# Sheet_1_2025-08-10.net
KiCad netlist of a schematic drawn in Altium Designer
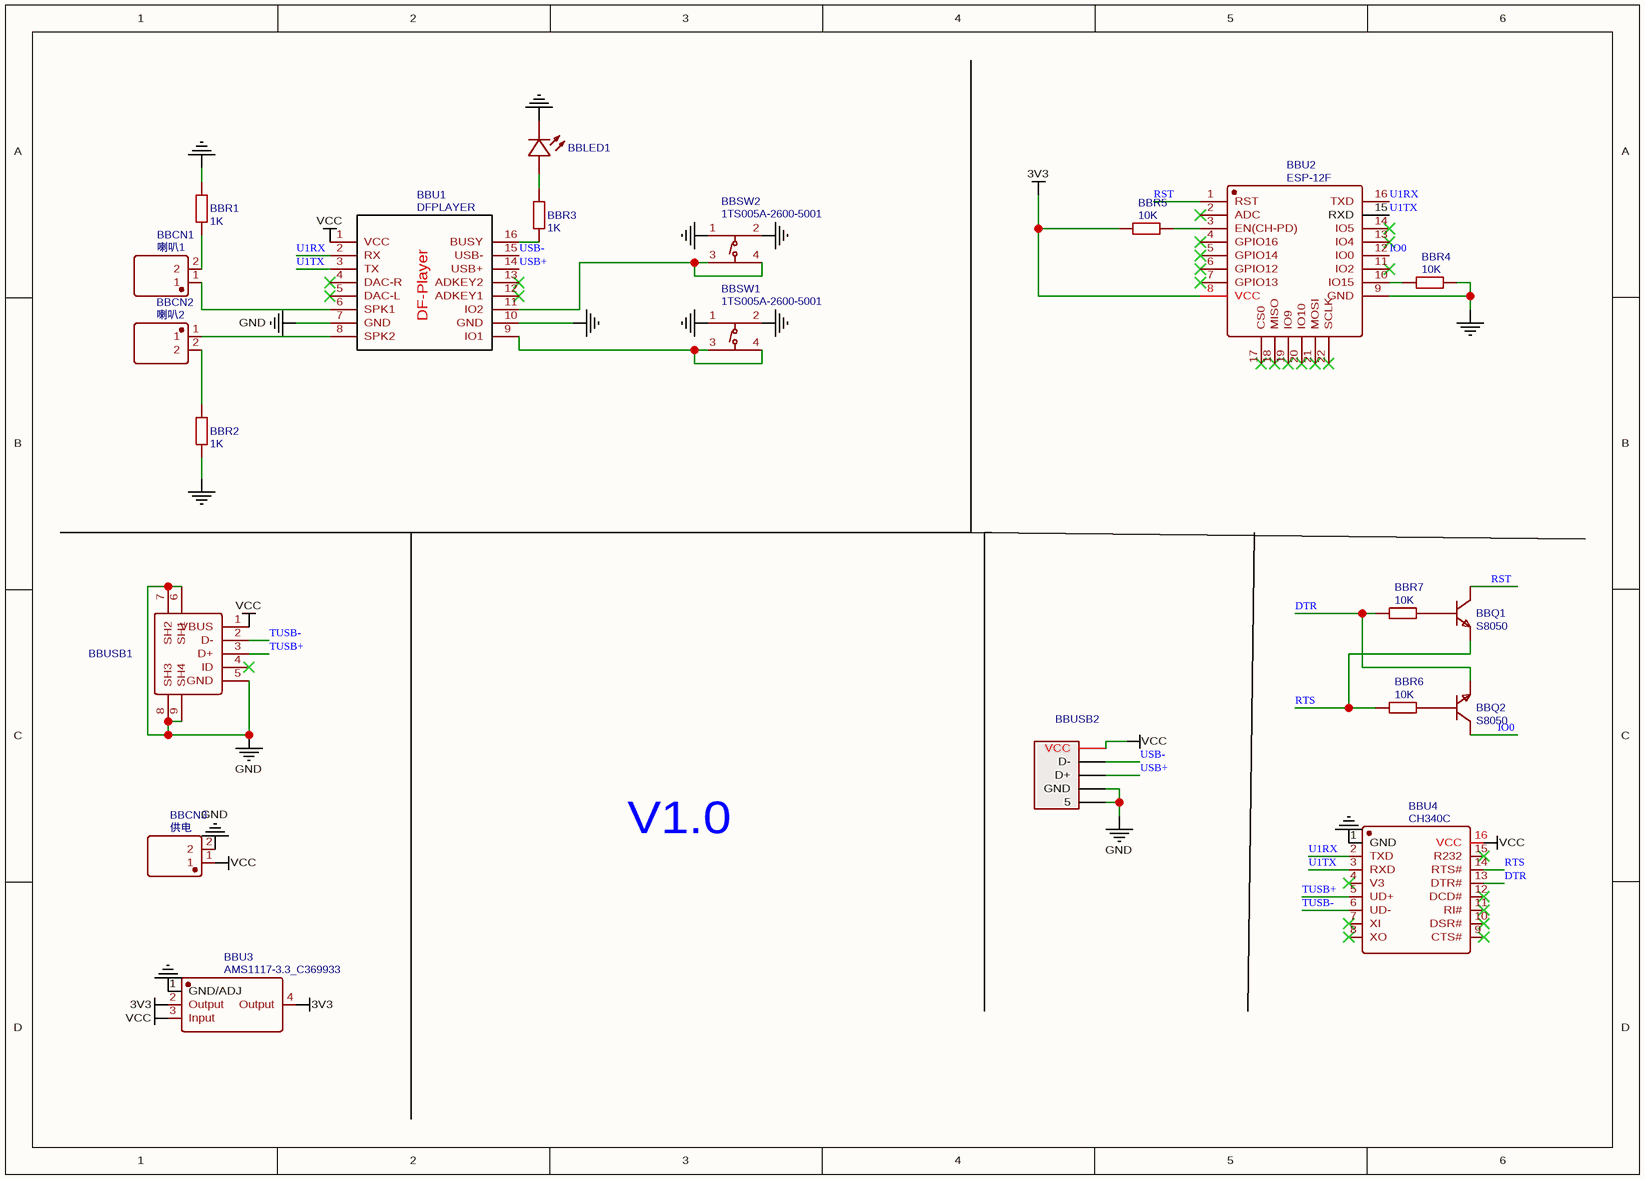
[diagram p0: Sheet_1_2025-08-10.schdoc]

(export (version "E")
  (design (tool "Eeschema 10.0.6"))
  (components
    (comp (ref "BBCN1")
      (value "喇叭1")
      (fields (field (name "MANUFACTURER") "Boom Precision Elec") (field (name "CONTRIBUTOR") "LCSC"))
      (libsource (lib "altium-import") (part "root_2_喇叭1_"))
    )
    (comp (ref "BBCN2")
      (value "喇叭2")
      (fields (field (name "MANUFACTURER") "Boom Precision Elec") (field (name "CONTRIBUTOR") "LCSC"))
      (libsource (lib "altium-import") (part "root_2_喇叭2_"))
    )
    (comp (ref "BBCN3")
      (value "供电")
      (fields (field (name "MANUFACTURER") "Boom Precision Elec") (field (name "CONTRIBUTOR") "LCSC"))
      (libsource (lib "altium-import") (part "root_2_供电_"))
    )
    (comp (ref "BBLED1")
      (value "FC-2012WBY-460G")
      (fields (field (name "MANUFACTURER") "NATIONSTAR"))
      (libsource (lib "altium-import") (part "root_3_FC-2012WBY-460G_"))
    )
    (comp (ref "BBQ1")
      (value "S8050")
      (fields (field (name "MANUFACTURER") "Yenji") (field (name "CONTRIBUTOR") "立创EDA官方封装库"))
      (libsource (lib "") (part "root_0_S8050__1"))
    )
    (comp (ref "BBQ2")
      (value "S8050")
      (fields (field (name "MANUFACTURER") "Yenji") (field (name "CONTRIBUTOR") "立创EDA官方封装库"))
      (libsource (lib "altium-import") (part "root_0_S8050_"))
    )
    (comp (ref "BBR1")
      (value "1K")
      (fields
        (field (name "MANUFACTURER") "LIZ Elec")
        (field (name "MANUFACTURER PART") "CR0805J80102G")
        (field (name "CONTRIBUTOR") "LCSC")
      )
      (libsource (lib "altium-import") (part "root_1_1K_"))
    )
    (comp (ref "BBR2")
      (value "1K")
      (fields
        (field (name "MANUFACTURER") "LIZ Elec")
        (field (name "MANUFACTURER PART") "CR0805J80102G")
        (field (name "CONTRIBUTOR") "LCSC")
      )
      (libsource (lib "altium-import") (part "root_3_1K_"))
    )
    (comp (ref "BBR3")
      (value "1K")
      (fields
        (field (name "MANUFACTURER") "LIZ Elec")
        (field (name "MANUFACTURER PART") "CR0805J80102G")
        (field (name "CONTRIBUTOR") "LCSC")
      )
      (libsource (lib "altium-import") (part "root_1_1K_"))
    )
    (comp (ref "BBR4")
      (value "10K")
      (fields
        (field (name "MANUFACTURER") "Stackpole Elec")
        (field (name "MANUFACTURER PART") "RMCF0603JT10K0")
        (field (name "CONTRIBUTOR") "LCSC")
      )
      (libsource (lib "altium-import") (part "root_0_10K_"))
    )
    (comp (ref "BBR5")
      (value "10K")
      (fields
        (field (name "MANUFACTURER") "Stackpole Elec")
        (field (name "MANUFACTURER PART") "RMCF0603JT10K0")
        (field (name "CONTRIBUTOR") "LCSC")
      )
      (libsource (lib "altium-import") (part "root_0_10K_"))
    )
    (comp (ref "BBR6")
      (value "10K")
      (fields
        (field (name "MANUFACTURER") "Stackpole Elec")
        (field (name "MANUFACTURER PART") "RMCF0603JT10K0")
        (field (name "CONTRIBUTOR") "LCSC")
      )
      (libsource (lib "altium-import") (part "root_0_10K_"))
    )
    (comp (ref "BBR7")
      (value "10K")
      (fields
        (field (name "MANUFACTURER") "Stackpole Elec")
        (field (name "MANUFACTURER PART") "RMCF0603JT10K0")
        (field (name "CONTRIBUTOR") "LCSC")
      )
      (libsource (lib "altium-import") (part "root_0_10K_"))
    )
    (comp (ref "BBSW1")
      (value "1TS005A-2600-5001")
      (fields (field (name "MANUFACTURER") "HYP") (field (name "CONTRIBUTOR") "LCSC"))
      (libsource (lib "altium-import") (part "root_0_1TS005A-2600-5001_"))
    )
    (comp (ref "BBSW2")
      (value "1TS005A-2600-5001")
      (fields (field (name "MANUFACTURER") "HYP") (field (name "CONTRIBUTOR") "LCSC"))
      (libsource (lib "altium-import") (part "root_0_1TS005A-2600-5001_"))
    )
    (comp (ref "BBU1")
      (value "DFPLAYER")
      (fields (field (name "CONTRIBUTOR") "walter471114"))
      (libsource (lib "altium-import") (part "root_0_DFPLAYER_"))
    )
    (comp (ref "BBU2")
      (value "ESP-12F")
      (fields
        (field (name "MANUFACTURER") "Ai-Thinker")
        (field (name "MANUFACTURER PART") "ESP-12F(ESP8266MOD)")
      )
      (libsource (lib "altium-import") (part "root_0_ESP-12F_"))
    )
    (comp (ref "BBU3")
      (value "AMS1117-3.3_C369933")
      (fields
        (field (name "MANUFACTURER") "KEXIN")
        (field (name "MANUFACTURER PART") "AMS1117-3.3")
        (field (name "CONTRIBUTOR") "LCSC")
      )
      (libsource (lib "altium-import") (part "root_0_AMS1117-3.3_C369933_"))
    )
    (comp (ref "BBU4")
      (value "CH340C")
      (fields (field (name "MANUFACTURER") "WCH"))
      (libsource (lib "altium-import") (part "root_0_CH340C_"))
    )
    (comp (ref "BBUSB1")
      (value "MICROQTJ")
      (fields
        (field (name "MANUFACTURER") "SHOU HAN")
        (field (name "MANUFACTURER PART") "MicroQTJ")
        (field (name "CONTRIBUTOR") "LCSC")
      )
      (libsource (lib "altium-import") (part "root_0_MICROQTJ_"))
    )
    (comp (ref "BBUSB2")
      (value "YJ-USB-AF-SMT-01")
      (fields (field (name "MANUFACTURER") "ValuePro"))
      (libsource (lib "altium-import") (part "root_0_YJ-USB-AF-SMT-01_"))
    )
  )
  (nets
    (net (code "1") (name "/DTR") (class "Default")
      (node (ref "BBQ2") (pin "2") (pinfunction "E_2") (pintype "passive"))
      (node (ref "BBR7") (pin "1") (pinfunction "1_1") (pintype "passive"))
      (node (ref "BBU4") (pin "13") (pinfunction "DTR#_13") (pintype "passive"))
    )
    (net (code "2") (name "/IO0") (class "Default")
      (node (ref "BBQ2") (pin "3") (pinfunction "C_3") (pintype "passive"))
      (node (ref "BBU2") (pin "12") (pinfunction "IO0_12") (pintype "passive"))
    )
    (net (code "3") (name "/RST") (class "Default")
      (node (ref "BBQ1") (pin "3") (pinfunction "C_3") (pintype "passive"))
      (node (ref "BBU2") (pin "1") (pinfunction "RST_1") (pintype "passive"))
    )
    (net (code "4") (name "/RTS") (class "Default")
      (node (ref "BBQ1") (pin "2") (pinfunction "E_2") (pintype "passive"))
      (node (ref "BBR6") (pin "1") (pinfunction "1_1") (pintype "passive"))
      (node (ref "BBU4") (pin "14") (pinfunction "RTS#_14") (pintype "passive"))
    )
    (net (code "5") (name "/TUSB+") (class "Default")
      (node (ref "BBU4") (pin "5") (pinfunction "UD+_5") (pintype "passive"))
      (node (ref "BBUSB1") (pin "3") (pinfunction "D+_3") (pintype "passive"))
    )
    (net (code "6") (name "/TUSB-") (class "Default")
      (node (ref "BBU4") (pin "6") (pinfunction "UD-_6") (pintype "passive"))
      (node (ref "BBUSB1") (pin "2") (pinfunction "D-_2") (pintype "passive"))
    )
    (net (code "7") (name "/U1RX") (class "Default")
      (node (ref "BBU1") (pin "2") (pinfunction "RX_2") (pintype "passive"))
      (node (ref "BBU2") (pin "16") (pinfunction "TXD_16") (pintype "passive"))
      (node (ref "BBU4") (pin "2") (pinfunction "TXD_2") (pintype "passive"))
    )
    (net (code "8") (name "/U1TX") (class "Default")
      (node (ref "BBU1") (pin "3") (pinfunction "TX_3") (pintype "passive"))
      (node (ref "BBU2") (pin "15") (pinfunction "RXD_15") (pintype "passive"))
      (node (ref "BBU4") (pin "3") (pinfunction "RXD_3") (pintype "passive"))
    )
    (net (code "9") (name "/USB+") (class "Default")
      (node (ref "BBU1") (pin "14") (pinfunction "USB+_14") (pintype "passive"))
      (node (ref "BBUSB2") (pin "3") (pinfunction "D+_3") (pintype "passive"))
    )
    (net (code "10") (name "/USB-") (class "Default")
      (node (ref "BBU1") (pin "15") (pinfunction "USB-_15") (pintype "passive"))
      (node (ref "BBUSB2") (pin "2") (pinfunction "D-_2") (pintype "passive"))
    )
    (net (code "11") (name "3V3") (class "Default")
      (node (ref "BBR5") (pin "1") (pinfunction "1_1") (pintype "passive"))
      (node (ref "BBU2") (pin "8") (pinfunction "VCC_8") (pintype "passive"))
      (node (ref "BBU3") (pin "2") (pinfunction "Output_2") (pintype "passive"))
      (node (ref "BBU3") (pin "4") (pinfunction "Output_4") (pintype "passive"))
    )
    (net (code "12") (name "GND") (class "Default")
      (node (ref "BBCN3") (pin "2") (pinfunction "2_2") (pintype "passive"))
      (node (ref "BBLED1") (pin "1") (pinfunction "-_1") (pintype "passive"))
      (node (ref "BBR1") (pin "2") (pinfunction "2_2") (pintype "passive"))
      (node (ref "BBR2") (pin "2") (pinfunction "2_2") (pintype "passive"))
      (node (ref "BBR4") (pin "2") (pinfunction "2_2") (pintype "passive"))
      (node (ref "BBSW1") (pin "1") (pinfunction "1_1") (pintype "passive"))
      (node (ref "BBSW1") (pin "2") (pinfunction "2_2") (pintype "passive"))
      (node (ref "BBSW2") (pin "1") (pinfunction "1_1") (pintype "passive"))
      (node (ref "BBSW2") (pin "2") (pinfunction "2_2") (pintype "passive"))
      (node (ref "BBU1") (pin "10") (pinfunction "GND_10") (pintype "passive"))
      (node (ref "BBU1") (pin "7") (pinfunction "GND_7") (pintype "passive"))
      (node (ref "BBU2") (pin "9") (pinfunction "GND_9") (pintype "passive"))
      (node (ref "BBU3") (pin "1") (pinfunction "GND/ADJ_1") (pintype "passive"))
      (node (ref "BBU4") (pin "1") (pinfunction "GND_1") (pintype "passive"))
      (node (ref "BBUSB1") (pin "5") (pinfunction "GND_5") (pintype "passive"))
      (node (ref "BBUSB1") (pin "6") (pinfunction "SH1_6") (pintype "passive"))
      (node (ref "BBUSB1") (pin "7") (pinfunction "SH2_7") (pintype "passive"))
      (node (ref "BBUSB1") (pin "8") (pinfunction "SH3_8") (pintype "passive"))
      (node (ref "BBUSB1") (pin "9") (pinfunction "SH4_9") (pintype "passive"))
      (node (ref "BBUSB2") (pin "4") (pinfunction "GND_4") (pintype "passive"))
      (node (ref "BBUSB2") (pin "5") (pinfunction "5_5") (pintype "passive"))
    )
    (net (code "13") (name "Net-(BBCN1-Pad2)") (class "Default")
      (node (ref "BBCN1") (pin "2") (pinfunction "2_2") (pintype "passive"))
      (node (ref "BBR1") (pin "1") (pinfunction "1_1") (pintype "passive"))
    )
    (net (code "14") (name "Net-(BBCN2-Pad2)") (class "Default")
      (node (ref "BBCN2") (pin "2") (pinfunction "2_2") (pintype "passive"))
      (node (ref "BBR2") (pin "1") (pinfunction "1_1") (pintype "passive"))
    )
    (net (code "15") (name "Net-(BBLED1-+)") (class "Default")
      (node (ref "BBLED1") (pin "2") (pinfunction "+_2") (pintype "passive"))
      (node (ref "BBR3") (pin "2") (pinfunction "2_2") (pintype "passive"))
    )
    (net (code "16") (name "Net-(BBQ1-B)") (class "Default")
      (node (ref "BBQ1") (pin "1") (pinfunction "B_1") (pintype "passive"))
      (node (ref "BBR7") (pin "2") (pinfunction "2_2") (pintype "passive"))
    )
    (net (code "17") (name "Net-(BBQ2-B)") (class "Default")
      (node (ref "BBQ2") (pin "1") (pinfunction "B_1") (pintype "passive"))
      (node (ref "BBR6") (pin "2") (pinfunction "2_2") (pintype "passive"))
    )
    (net (code "18") (name "Net-(BBU1-BUSY)") (class "Default")
      (node (ref "BBR3") (pin "1") (pinfunction "1_1") (pintype "passive"))
      (node (ref "BBU1") (pin "16") (pinfunction "BUSY_16") (pintype "passive"))
    )
    (net (code "19") (name "Net-(BBU1-IO1)") (class "Default")
      (node (ref "BBSW1") (pin "3") (pinfunction "3_3") (pintype "passive"))
      (node (ref "BBSW1") (pin "4") (pinfunction "4_4") (pintype "passive"))
      (node (ref "BBU1") (pin "9") (pinfunction "IO1_9") (pintype "passive"))
    )
    (net (code "20") (name "Net-(BBU1-IO2)") (class "Default")
      (node (ref "BBSW2") (pin "3") (pinfunction "3_3") (pintype "passive"))
      (node (ref "BBSW2") (pin "4") (pinfunction "4_4") (pintype "passive"))
      (node (ref "BBU1") (pin "11") (pinfunction "IO2_11") (pintype "passive"))
    )
    (net (code "21") (name "Net-(BBU1-SPK1)") (class "Default")
      (node (ref "BBCN1") (pin "1") (pinfunction "1_1") (pintype "passive"))
      (node (ref "BBU1") (pin "6") (pinfunction "SPK1_6") (pintype "passive"))
    )
    (net (code "22") (name "Net-(BBU1-SPK2)") (class "Default")
      (node (ref "BBCN2") (pin "1") (pinfunction "1_1") (pintype "passive"))
      (node (ref "BBU1") (pin "8") (pinfunction "SPK2_8") (pintype "passive"))
    )
    (net (code "23") (name "Net-(BBU2-EN(CH-PD))") (class "Default")
      (node (ref "BBR5") (pin "2") (pinfunction "2_2") (pintype "passive"))
      (node (ref "BBU2") (pin "3") (pinfunction "EN(CH-PD)_3") (pintype "passive"))
    )
    (net (code "24") (name "Net-(BBU2-IO15)") (class "Default")
      (node (ref "BBR4") (pin "1") (pinfunction "1_1") (pintype "passive"))
      (node (ref "BBU2") (pin "10") (pinfunction "IO15_10") (pintype "passive"))
    )
    (net (code "25") (name "VCC") (class "Default")
      (node (ref "BBCN3") (pin "1") (pinfunction "1_1") (pintype "passive"))
      (node (ref "BBU1") (pin "1") (pinfunction "VCC_1") (pintype "passive"))
      (node (ref "BBU3") (pin "3") (pinfunction "Input_3") (pintype "passive"))
      (node (ref "BBU4") (pin "16") (pinfunction "VCC_16") (pintype "passive"))
      (node (ref "BBUSB1") (pin "1") (pinfunction "VBUS_1") (pintype "passive"))
      (node (ref "BBUSB2") (pin "1") (pinfunction "VCC_1") (pintype "passive"))
    )
    (net (code "26") (name "unconnected-(BBU1-ADKEY1-Pad12)") (class "Default")
      (node (ref "BBU1") (pin "12") (pinfunction "ADKEY1_12") (pintype "passive+no_connect"))
    )
    (net (code "27") (name "unconnected-(BBU1-ADKEY2-Pad13)") (class "Default")
      (node (ref "BBU1") (pin "13") (pinfunction "ADKEY2_13") (pintype "passive+no_connect"))
    )
    (net (code "28") (name "unconnected-(BBU1-DAC-L-Pad5)") (class "Default")
      (node (ref "BBU1") (pin "5") (pinfunction "DAC-L_5") (pintype "passive+no_connect"))
    )
    (net (code "29") (name "unconnected-(BBU1-DAC-R-Pad4)") (class "Default")
      (node (ref "BBU1") (pin "4") (pinfunction "DAC-R_4") (pintype "passive+no_connect"))
    )
    (net (code "30") (name "unconnected-(BBU2-ADC-Pad2)") (class "Default")
      (node (ref "BBU2") (pin "2") (pinfunction "ADC_2") (pintype "passive+no_connect"))
    )
    (net (code "31") (name "unconnected-(BBU2-CS0-Pad17)") (class "Default")
      (node (ref "BBU2") (pin "17") (pinfunction "CS0_17") (pintype "passive+no_connect"))
    )
    (net (code "32") (name "unconnected-(BBU2-GPIO12-Pad6)") (class "Default")
      (node (ref "BBU2") (pin "6") (pinfunction "GPIO12_6") (pintype "passive+no_connect"))
    )
    (net (code "33") (name "unconnected-(BBU2-GPIO13-Pad7)") (class "Default")
      (node (ref "BBU2") (pin "7") (pinfunction "GPIO13_7") (pintype "passive+no_connect"))
    )
    (net (code "34") (name "unconnected-(BBU2-GPIO14-Pad5)") (class "Default")
      (node (ref "BBU2") (pin "5") (pinfunction "GPIO14_5") (pintype "passive+no_connect"))
    )
    (net (code "35") (name "unconnected-(BBU2-GPIO16-Pad4)") (class "Default")
      (node (ref "BBU2") (pin "4") (pinfunction "GPIO16_4") (pintype "passive+no_connect"))
    )
    (net (code "36") (name "unconnected-(BBU2-IO2-Pad11)") (class "Default")
      (node (ref "BBU2") (pin "11") (pinfunction "IO2_11") (pintype "passive+no_connect"))
    )
    (net (code "37") (name "unconnected-(BBU2-IO4-Pad13)") (class "Default")
      (node (ref "BBU2") (pin "13") (pinfunction "IO4_13") (pintype "passive+no_connect"))
    )
    (net (code "38") (name "unconnected-(BBU2-IO5-Pad14)") (class "Default")
      (node (ref "BBU2") (pin "14") (pinfunction "IO5_14") (pintype "passive+no_connect"))
    )
    (net (code "39") (name "unconnected-(BBU2-IO9-Pad19)") (class "Default")
      (node (ref "BBU2") (pin "19") (pinfunction "IO9_19") (pintype "passive+no_connect"))
    )
    (net (code "40") (name "unconnected-(BBU2-IO10-Pad20)") (class "Default")
      (node (ref "BBU2") (pin "20") (pinfunction "IO10_20") (pintype "passive+no_connect"))
    )
    (net (code "41") (name "unconnected-(BBU2-MISO-Pad18)") (class "Default")
      (node (ref "BBU2") (pin "18") (pinfunction "MISO_18") (pintype "passive+no_connect"))
    )
    (net (code "42") (name "unconnected-(BBU2-MOSI-Pad21)") (class "Default")
      (node (ref "BBU2") (pin "21") (pinfunction "MOSI_21") (pintype "passive+no_connect"))
    )
    (net (code "43") (name "unconnected-(BBU2-SCLK-Pad22)") (class "Default")
      (node (ref "BBU2") (pin "22") (pinfunction "SCLK_22") (pintype "passive+no_connect"))
    )
    (net (code "44") (name "unconnected-(BBU4-CTS#-Pad9)") (class "Default")
      (node (ref "BBU4") (pin "9") (pinfunction "CTS#_9") (pintype "passive+no_connect"))
    )
    (net (code "45") (name "unconnected-(BBU4-DCD#-Pad12)") (class "Default")
      (node (ref "BBU4") (pin "12") (pinfunction "DCD#_12") (pintype "passive+no_connect"))
    )
    (net (code "46") (name "unconnected-(BBU4-DSR#-Pad10)") (class "Default")
      (node (ref "BBU4") (pin "10") (pinfunction "DSR#_10") (pintype "passive+no_connect"))
    )
    (net (code "47") (name "unconnected-(BBU4-R232-Pad15)") (class "Default")
      (node (ref "BBU4") (pin "15") (pinfunction "R232_15") (pintype "passive+no_connect"))
    )
    (net (code "48") (name "unconnected-(BBU4-RI#-Pad11)") (class "Default")
      (node (ref "BBU4") (pin "11") (pinfunction "RI#_11") (pintype "passive+no_connect"))
    )
    (net (code "49") (name "unconnected-(BBU4-V3-Pad4)") (class "Default")
      (node (ref "BBU4") (pin "4") (pinfunction "V3_4") (pintype "passive+no_connect"))
    )
    (net (code "50") (name "unconnected-(BBU4-XI-Pad7)") (class "Default")
      (node (ref "BBU4") (pin "7") (pinfunction "XI_7") (pintype "passive+no_connect"))
    )
    (net (code "51") (name "unconnected-(BBU4-XO-Pad8)") (class "Default")
      (node (ref "BBU4") (pin "8") (pinfunction "XO_8") (pintype "passive+no_connect"))
    )
    (net (code "52") (name "unconnected-(BBUSB1-ID-Pad4)") (class "Default")
      (node (ref "BBUSB1") (pin "4") (pinfunction "ID_4") (pintype "passive+no_connect"))
    )
  )
)
